# 1-Power.net
KiCad netlist of a schematic drawn in Altium Designer
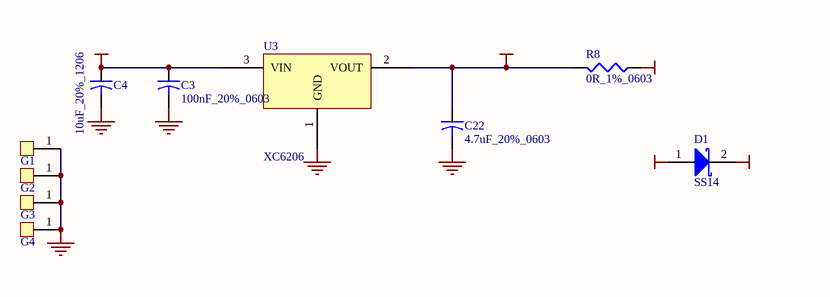
[diagram p0: 1-Power.SCHDOC]

(export (version "E")
  (design (tool "Eeschema 10.0.6"))
  (components
    (comp (ref "C3")
      (value "100nF_20%_0603")
      (footprint "C1608-0603")
      (description "Capacitor")
      (fields (field (name "PUBLISHER") "Altium Limited"))
      (libsource (lib "Miscellaneous Devices") (part "Cap2"))
    )
    (comp (ref "C4")
      (value "10uF_20%_1206")
      (footprint "CC3216-1206")
      (description "Capacitor")
      (fields (field (name "PUBLISHER") "Altium Limited"))
      (libsource (lib "Miscellaneous Devices") (part "Cap2"))
    )
    (comp (ref "C22")
      (value "4.7uF_20%_0603")
      (footprint "C1608-0603")
      (description "Capacitor")
      (fields (field (name "PUBLISHER") "Altium Limited"))
      (libsource (lib "Miscellaneous Devices") (part "Cap2"))
    )
    (comp (ref "D1")
      (value "SS14")
      (footprint "LED0805")
      (description "Schottky Diode")
      (fields (field (name "PUBLISHER") "Altium Limited"))
      (libsource (lib "Miscellaneous Devices") (part "D Schottky"))
    )
    (comp (ref "G1") (value "ND") (footprint "END_3_6") (libsource (lib "Device") (part "ND")))
    (comp (ref "G2") (value "ND") (footprint "END_3_6") (libsource (lib "Device") (part "ND")))
    (comp (ref "G3") (value "ND") (footprint "END_3_6") (libsource (lib "Device") (part "ND")))
    (comp (ref "G4") (value "ND") (footprint "END_3_6") (libsource (lib "Device") (part "ND")))
    (comp (ref "R8")
      (value "0R_1%_0603")
      (footprint "C1608-0603")
      (description "Resistor")
      (fields (field (name "PUBLISHER") "Altium Limited"))
      (libsource (lib "Miscellaneous Devices") (part "Res3"))
    )
    (comp (ref "U3") (value "XC6206") (footprint "SO-G3/C2.5") (libsource (lib "Device") (part "XC6206")))
  )
  (nets
    (net (code "1") (name "GND") (class "Default")
      (node (ref "C22") (pin "2") (pinfunction "2_2") (pintype "passive"))
      (node (ref "C3") (pin "2") (pinfunction "2_2") (pintype "passive"))
      (node (ref "C4") (pin "2") (pinfunction "2_2") (pintype "passive"))
      (node (ref "G1") (pin "1") (pinfunction "SW_1") (pintype "passive"))
      (node (ref "G2") (pin "1") (pinfunction "SW_1") (pintype "passive"))
      (node (ref "G3") (pin "1") (pinfunction "SW_1") (pintype "passive"))
      (node (ref "G4") (pin "1") (pinfunction "SW_1") (pintype "passive"))
      (node (ref "U3") (pin "1") (pinfunction "GND_1") (pintype "passive"))
    )
    (net (code "2") (name "VCC_2V8") (class "Default")
      (node (ref "C22") (pin "1") (pinfunction "1_1") (pintype "passive"))
      (node (ref "R8") (pin "2") (pinfunction "2_2") (pintype "passive"))
      (node (ref "U3") (pin "2") (pinfunction "VOUT_2") (pintype "passive"))
    )
    (net (code "3") (name "VCC_5V") (class "Default")
      (node (ref "C3") (pin "1") (pinfunction "1_1") (pintype "passive"))
      (node (ref "C4") (pin "1") (pinfunction "1_1") (pintype "passive"))
      (node (ref "D1") (pin "1") (pinfunction "A_1") (pintype "passive"))
      (node (ref "U3") (pin "3") (pinfunction "VIN_3") (pintype "passive"))
    )
    (net (code "4") (name "VCC_MCU") (class "Default")
      (node (ref "R8") (pin "1") (pinfunction "1_1") (pintype "passive"))
    )
    (net (code "5") (name "VCC_TH") (class "Default")
      (node (ref "D1") (pin "2") (pinfunction "K_2") (pintype "passive"))
    )
  )
)
